# SensorsPower.net
KiCad netlist of a schematic drawn in Altium Designer
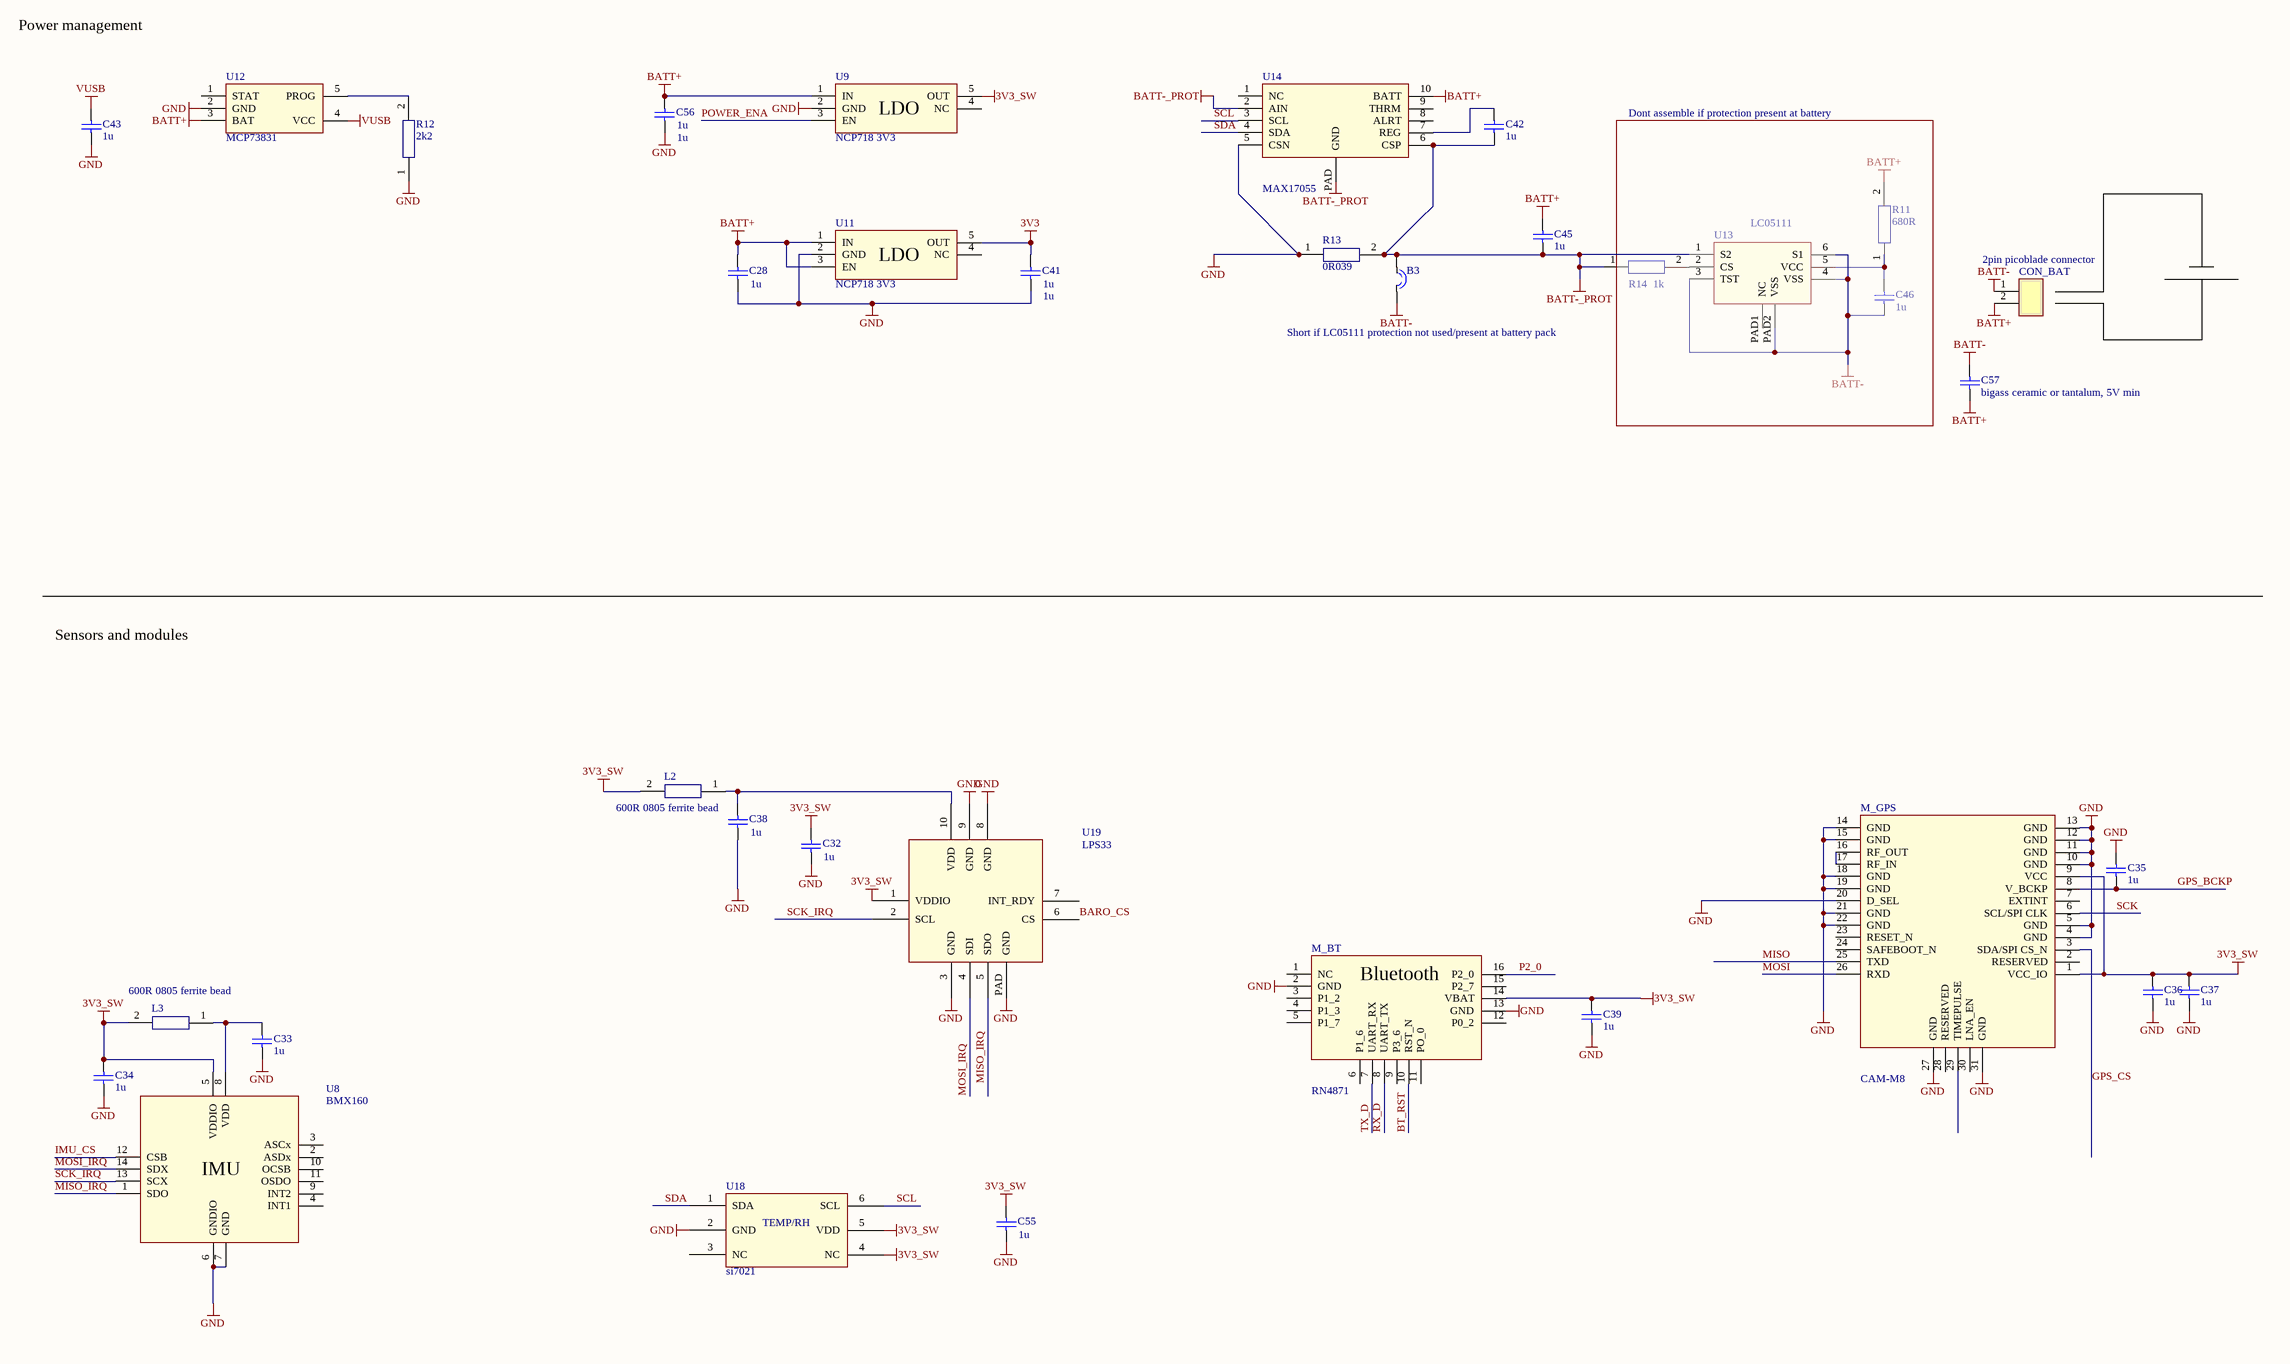
[diagram p0: SensorsPower.SchDoc]

(export (version "E")
  (design (tool "Eeschema 10.0.6"))
  (components
    (comp (ref "B3")
      (value "Short if LC05111 protection not used/present at battery pack")
      (footprint "Solder_bridge_small")
      (description "Solder bridge")
      (libsource (lib "xilinx") (part "Solder_bridge"))
    )
    (comp (ref "C28")
      (value "1u")
      (footprint "cap0603")
      (description "0603")
      (fields (field (name "PUBLISHER") "Altium Limited"))
      (libsource (lib "Miscellaneous Devices") (part "Cap"))
    )
    (comp (ref "C32")
      (value "1u")
      (footprint "cap0603")
      (description "0603")
      (fields (field (name "PUBLISHER") "Altium Limited"))
      (libsource (lib "Miscellaneous Devices") (part "Cap"))
    )
    (comp (ref "C33")
      (value "1u")
      (footprint "cap0603")
      (description "0603")
      (fields (field (name "PUBLISHER") "Altium Limited"))
      (libsource (lib "Miscellaneous Devices") (part "Cap"))
    )
    (comp (ref "C34")
      (value "1u")
      (footprint "cap0603")
      (description "0603")
      (fields (field (name "PUBLISHER") "Altium Limited"))
      (libsource (lib "Miscellaneous Devices") (part "Cap"))
    )
    (comp (ref "C35")
      (value "1u")
      (footprint "cap0603")
      (description "0603")
      (fields (field (name "PUBLISHER") "Altium Limited"))
      (libsource (lib "Miscellaneous Devices") (part "Cap"))
    )
    (comp (ref "C36")
      (value "1u")
      (footprint "cap0603")
      (description "0603")
      (fields (field (name "PUBLISHER") "Altium Limited"))
      (libsource (lib "Miscellaneous Devices") (part "Cap"))
    )
    (comp (ref "C37")
      (value "1u")
      (footprint "cap0603")
      (description "0603")
      (fields (field (name "PUBLISHER") "Altium Limited"))
      (libsource (lib "Miscellaneous Devices") (part "Cap"))
    )
    (comp (ref "C38")
      (value "1u")
      (footprint "cap0603")
      (description "0603")
      (fields (field (name "PUBLISHER") "Altium Limited"))
      (libsource (lib "Miscellaneous Devices") (part "Cap"))
    )
    (comp (ref "C39")
      (value "1u")
      (footprint "cap0603")
      (description "0603")
      (fields (field (name "PUBLISHER") "Altium Limited"))
      (libsource (lib "Miscellaneous Devices") (part "Cap"))
    )
    (comp (ref "C41")
      (value "1u")
      (footprint "cap0603")
      (description "0603")
      (fields (field (name "ALTIUM_VALUE") "1u") (field (name "PUBLISHER") "Altium Limited"))
      (libsource (lib "Miscellaneous Devices") (part "Cap"))
    )
    (comp (ref "C42")
      (value "1u")
      (footprint "cap0603")
      (description "0603")
      (fields (field (name "PUBLISHER") "Altium Limited"))
      (libsource (lib "Miscellaneous Devices") (part "Cap"))
    )
    (comp (ref "C43")
      (value "1u")
      (footprint "cap0603")
      (description "0603")
      (fields (field (name "PUBLISHER") "Altium Limited"))
      (libsource (lib "Miscellaneous Devices") (part "Cap"))
    )
    (comp (ref "C45")
      (value "1u")
      (footprint "cap0603")
      (description "0603")
      (fields (field (name "PUBLISHER") "Altium Limited"))
      (libsource (lib "Miscellaneous Devices") (part "Cap"))
    )
    (comp (ref "C46")
      (value "1u")
      (footprint "cap0603")
      (description "0603")
      (fields (field (name "PUBLISHER") "Altium Limited"))
      (libsource (lib "Miscellaneous Devices") (part "Cap"))
    )
    (comp (ref "C55")
      (value "1u")
      (footprint "cap0603")
      (description "0603")
      (fields (field (name "PUBLISHER") "Altium Limited"))
      (libsource (lib "Miscellaneous Devices") (part "Cap"))
    )
    (comp (ref "C56")
      (value "1u")
      (footprint "cap0603")
      (description "0603")
      (fields (field (name "ALTIUM_VALUE") "1u") (field (name "PUBLISHER") "Altium Limited"))
      (libsource (lib "Miscellaneous Devices") (part "Cap"))
    )
    (comp (ref "C57")
      (value "bigass ceramic or tantalum, 5V min")
      (footprint "CAP1206")
      (description "1206")
      (fields (field (name "PUBLISHER") "Altium Limited"))
      (libsource (lib "Miscellaneous Devices") (part "Cap"))
    )
    (comp (ref "CON_BAT")
      (value "2pin picoblade connector")
      (footprint "1x2, 1.25")
      (libsource (lib "headers") (part "1x2 Header, 2.54"))
    )
    (comp (ref "L2")
      (value "600R 0805 ferrite bead")
      (footprint "cap0805")
      (description "0805")
      (libsource (lib "PassiveSMT") (part "Resistor1"))
    )
    (comp (ref "L3")
      (value "600R 0805 ferrite bead")
      (footprint "cap0805")
      (description "0805")
      (libsource (lib "PassiveSMT") (part "Resistor1"))
    )
    (comp (ref "M_BT")
      (value "RN4871")
      (footprint "RN4871")
      (description "bluetooth module")
      (libsource (lib "xilinx") (part "RN4871"))
    )
    (comp (ref "M_GPS")
      (value "CAM-M8")
      (footprint "CAM")
      (description "u-blox CAM GNSS antenna module")
      (fields (field (name "MANUFACTURER") "u-blox"))
      (libsource (lib "ubloxLib") (part "CAM-M8"))
    )
    (comp (ref "R11")
      (value "680R")
      (footprint "cap0805")
      (description "0805")
      (libsource (lib "PassiveSMT") (part "Resistor1"))
    )
    (comp (ref "R12")
      (value "2k2")
      (footprint "cap0805")
      (description "0805")
      (libsource (lib "PassiveSMT") (part "Resistor1"))
    )
    (comp (ref "R13")
      (value "0R039")
      (footprint "cap0805")
      (description "0805")
      (libsource (lib "PassiveSMT") (part "Resistor1"))
    )
    (comp (ref "R14")
      (value "1k")
      (footprint "cap0805")
      (description "0805")
      (libsource (lib "PassiveSMT") (part "Resistor1"))
    )
    (comp (ref "U8")
      (value "BMX160")
      (footprint "LGA14 3*2.5")
      (description "IMU mems unit")
      (libsource (lib "xilinx") (part "BMX160"))
    )
    (comp (ref "U9")
      (value "NCP718 3V3")
      (footprint "sot23-5")
      (description "SOT23 3.3V LDO regulator")
      (libsource (lib "xilinx") (part "LDLN025 LDO"))
    )
    (comp (ref "U11")
      (value "NCP718 3V3")
      (footprint "sot23-5")
      (description "SOT23 3.3V LDO regulator")
      (libsource (lib "xilinx") (part "LDLN025 LDO"))
    )
    (comp (ref "U12")
      (value "MCP73831")
      (footprint "sot23-5")
      (description "SOT23 linear battery charging controller")
      (libsource (lib "xilinx") (part "MCP73831"))
    )
    (comp (ref "U13")
      (value "LC05111")
      (footprint "wdfn6_dual_flag")
      (description "Battery protection circuit")
      (libsource (lib "xilinx") (part "LC05111"))
    )
    (comp (ref "U14")
      (value "MAX17055")
      (footprint "tdfn10_ep")
      (description "Battery monitoring gauge")
      (libsource (lib "xilinx") (part "MAX17055"))
    )
    (comp (ref "U18")
      (value "si7021")
      (footprint "dfn6")
      (description "temp and humidity sensor")
      (libsource (lib "xilinx") (part "SHT21"))
    )
    (comp (ref "U19")
      (value "LPS33")
      (footprint "LPS33")
      (description "barometer")
      (libsource (lib "xilinx") (part "LPS33"))
    )
  )
  (nets
    (net (code "1") (name "/BARO_CS") (class "Default")
      (node (ref "U19") (pin "6") (pinfunction "CS_6") (pintype "passive"))
    )
    (net (code "2") (name "/BT_RST") (class "Default")
      (node (ref "M_BT") (pin "10") (pinfunction "RST_N_10") (pintype "passive"))
    )
    (net (code "3") (name "/GPS_BCKP") (class "Default")
      (node (ref "C35") (pin "2") (pinfunction "2_2") (pintype "passive"))
      (node (ref "M_GPS") (pin "8") (pinfunction "V_BCKP_8") (pintype "passive"))
    )
    (net (code "4") (name "/GPS_CS") (class "Default")
      (node (ref "M_GPS") (pin "3") (pinfunction "SDA/SPI_CS_N_3") (pintype "passive"))
    )
    (net (code "5") (name "/IMU_CS") (class "Default")
      (node (ref "U8") (pin "12") (pinfunction "CSB_12") (pintype "passive"))
    )
    (net (code "6") (name "/MISO") (class "Default")
      (node (ref "M_GPS") (pin "25") (pinfunction "TXD_25") (pintype "passive"))
    )
    (net (code "7") (name "/MISO_IRQ") (class "Default")
      (node (ref "U19") (pin "5") (pinfunction "SDO_5") (pintype "passive"))
      (node (ref "U8") (pin "1") (pinfunction "SDO_1") (pintype "passive"))
    )
    (net (code "8") (name "/MOSI") (class "Default")
      (node (ref "M_GPS") (pin "26") (pinfunction "RXD_26") (pintype "passive"))
    )
    (net (code "9") (name "/MOSI_IRQ") (class "Default")
      (node (ref "U19") (pin "4") (pinfunction "SDI_4") (pintype "passive"))
      (node (ref "U8") (pin "14") (pinfunction "SDX_14") (pintype "passive"))
    )
    (net (code "10") (name "/P2_0") (class "Default")
      (node (ref "M_BT") (pin "16") (pinfunction "P2_0_16") (pintype "passive"))
    )
    (net (code "11") (name "/POWER_ENA") (class "Default")
      (node (ref "U9") (pin "3") (pinfunction "EN_3") (pintype "passive"))
    )
    (net (code "12") (name "/RX_D") (class "Default")
      (node (ref "M_BT") (pin "8") (pinfunction "UART_TX_8") (pintype "passive"))
    )
    (net (code "13") (name "/SCK") (class "Default")
      (node (ref "M_GPS") (pin "6") (pinfunction "SCL/SPI_CLK_6") (pintype "passive"))
    )
    (net (code "14") (name "/SCK_IRQ") (class "Default")
      (node (ref "U19") (pin "2") (pinfunction "SCL_2") (pintype "passive"))
      (node (ref "U8") (pin "13") (pinfunction "SCX_13") (pintype "passive"))
    )
    (net (code "15") (name "/SCL") (class "Default")
      (node (ref "U14") (pin "3") (pinfunction "SCL_3") (pintype "passive"))
      (node (ref "U18") (pin "6") (pinfunction "SCL_6") (pintype "passive"))
    )
    (net (code "16") (name "/SDA") (class "Default")
      (node (ref "U14") (pin "4") (pinfunction "SDA_4") (pintype "passive"))
      (node (ref "U18") (pin "1") (pinfunction "SDA_1") (pintype "passive"))
    )
    (net (code "17") (name "/TX_D") (class "Default")
      (node (ref "M_BT") (pin "7") (pinfunction "UART_RX_7") (pintype "passive"))
    )
    (net (code "18") (name "3V3") (class "Default")
      (node (ref "C41") (pin "2") (pinfunction "2_2") (pintype "passive"))
      (node (ref "U11") (pin "5") (pinfunction "OUT_5") (pintype "passive"))
    )
    (net (code "19") (name "3V3_SW") (class "Default")
      (node (ref "C32") (pin "2") (pinfunction "2_2") (pintype "passive"))
      (node (ref "C34") (pin "2") (pinfunction "2_2") (pintype "passive"))
      (node (ref "C36") (pin "1") (pinfunction "1_1") (pintype "passive"))
      (node (ref "C37") (pin "1") (pinfunction "1_1") (pintype "passive"))
      (node (ref "C39") (pin "1") (pinfunction "1_1") (pintype "passive"))
      (node (ref "C55") (pin "2") (pinfunction "2_2") (pintype "passive"))
      (node (ref "L2") (pin "2") (pinfunction "2_2") (pintype "passive"))
      (node (ref "L3") (pin "2") (pinfunction "2_2") (pintype "passive"))
      (node (ref "M_BT") (pin "14") (pinfunction "VBAT_14") (pintype "passive"))
      (node (ref "M_GPS") (pin "1") (pinfunction "VCC_IO_1") (pintype "passive"))
      (node (ref "M_GPS") (pin "9") (pinfunction "VCC_9") (pintype "passive"))
      (node (ref "U18") (pin "4") (pinfunction "NC_4") (pintype "passive"))
      (node (ref "U18") (pin "5") (pinfunction "VDD_5") (pintype "passive"))
      (node (ref "U19") (pin "1") (pinfunction "VDDIO_1") (pintype "passive"))
      (node (ref "U8") (pin "5") (pinfunction "VDDIO_5") (pintype "passive"))
      (node (ref "U9") (pin "5") (pinfunction "OUT_5") (pintype "passive"))
    )
    (net (code "20") (name "BATT+") (class "Default")
      (node (ref "C28") (pin "2") (pinfunction "2_2") (pintype "passive"))
      (node (ref "C45") (pin "2") (pinfunction "2_2") (pintype "passive"))
      (node (ref "C56") (pin "2") (pinfunction "2_2") (pintype "passive"))
      (node (ref "C57") (pin "1") (pinfunction "1_1") (pintype "passive"))
      (node (ref "CON_BAT") (pin "2") (pinfunction "2_2") (pintype "passive"))
      (node (ref "R11") (pin "2") (pinfunction "2_2") (pintype "passive"))
      (node (ref "U11") (pin "1") (pinfunction "IN_1") (pintype "passive"))
      (node (ref "U11") (pin "3") (pinfunction "EN_3") (pintype "passive"))
      (node (ref "U12") (pin "3") (pinfunction "BAT_3") (pintype "passive"))
      (node (ref "U14") (pin "10") (pinfunction "BATT_10") (pintype "passive"))
      (node (ref "U9") (pin "1") (pinfunction "IN_1") (pintype "passive"))
    )
    (net (code "21") (name "BATT-") (class "Default")
      (node (ref "B3") (pin "1") (pinfunction "1_1") (pintype "passive"))
      (node (ref "C46") (pin "1") (pinfunction "1_1") (pintype "passive"))
      (node (ref "C57") (pin "2") (pinfunction "2_2") (pintype "passive"))
      (node (ref "CON_BAT") (pin "1") (pinfunction "1_1") (pintype "passive"))
      (node (ref "U13") (pin "3") (pinfunction "TST_3") (pintype "passive"))
      (node (ref "U13") (pin "4") (pinfunction "VSS_4") (pintype "passive"))
      (node (ref "U13") (pin "6") (pinfunction "S1_6") (pintype "passive"))
      (node (ref "U13") (pin "PAD2") (pinfunction "VSS_PAD2") (pintype "passive"))
    )
    (net (code "22") (name "BATT-_PROT") (class "Default")
      (node (ref "B3") (pin "2") (pinfunction "2_2") (pintype "passive"))
      (node (ref "C42") (pin "1") (pinfunction "1_1") (pintype "passive"))
      (node (ref "C45") (pin "1") (pinfunction "1_1") (pintype "passive"))
      (node (ref "R13") (pin "2") (pinfunction "2_2") (pintype "passive"))
      (node (ref "R14") (pin "1") (pinfunction "1_1") (pintype "passive"))
      (node (ref "U13") (pin "1") (pinfunction "S2_1") (pintype "passive"))
      (node (ref "U14") (pin "2") (pinfunction "AIN_2") (pintype "passive"))
      (node (ref "U14") (pin "6") (pinfunction "CSP_6") (pintype "passive"))
      (node (ref "U14") (pin "PAD") (pinfunction "GND_PAD") (pintype "passive"))
    )
    (net (code "23") (name "GND") (class "Default")
      (node (ref "C28") (pin "1") (pinfunction "1_1") (pintype "passive"))
      (node (ref "C32") (pin "1") (pinfunction "1_1") (pintype "passive"))
      (node (ref "C33") (pin "1") (pinfunction "1_1") (pintype "passive"))
      (node (ref "C34") (pin "1") (pinfunction "1_1") (pintype "passive"))
      (node (ref "C35") (pin "1") (pinfunction "1_1") (pintype "passive"))
      (node (ref "C36") (pin "2") (pinfunction "2_2") (pintype "passive"))
      (node (ref "C37") (pin "2") (pinfunction "2_2") (pintype "passive"))
      (node (ref "C38") (pin "1") (pinfunction "1_1") (pintype "passive"))
      (node (ref "C39") (pin "2") (pinfunction "2_2") (pintype "passive"))
      (node (ref "C41") (pin "1") (pinfunction "1_1") (pintype "passive"))
      (node (ref "C43") (pin "1") (pinfunction "1_1") (pintype "passive"))
      (node (ref "C55") (pin "1") (pinfunction "1_1") (pintype "passive"))
      (node (ref "C56") (pin "1") (pinfunction "1_1") (pintype "passive"))
      (node (ref "M_BT") (pin "13") (pinfunction "GND_13") (pintype "passive"))
      (node (ref "M_BT") (pin "2") (pinfunction "GND_2") (pintype "passive"))
      (node (ref "M_GPS") (pin "10") (pinfunction "GND_10") (pintype "passive"))
      (node (ref "M_GPS") (pin "11") (pinfunction "GND_11") (pintype "passive"))
      (node (ref "M_GPS") (pin "12") (pinfunction "GND_12") (pintype "passive"))
      (node (ref "M_GPS") (pin "13") (pinfunction "GND_13") (pintype "passive"))
      (node (ref "M_GPS") (pin "14") (pinfunction "GND_14") (pintype "passive"))
      (node (ref "M_GPS") (pin "15") (pinfunction "GND_15") (pintype "passive"))
      (node (ref "M_GPS") (pin "18") (pinfunction "GND_18") (pintype "passive"))
      (node (ref "M_GPS") (pin "19") (pinfunction "GND_19") (pintype "passive"))
      (node (ref "M_GPS") (pin "20") (pinfunction "D_SEL_20") (pintype "passive"))
      (node (ref "M_GPS") (pin "21") (pinfunction "GND_21") (pintype "passive"))
      (node (ref "M_GPS") (pin "22") (pinfunction "GND_22") (pintype "passive"))
      (node (ref "M_GPS") (pin "27") (pinfunction "GND_27") (pintype "passive"))
      (node (ref "M_GPS") (pin "31") (pinfunction "GND_31") (pintype "passive"))
      (node (ref "M_GPS") (pin "4") (pinfunction "GND_4") (pintype "passive"))
      (node (ref "M_GPS") (pin "5") (pinfunction "GND_5") (pintype "passive"))
      (node (ref "R12") (pin "1") (pinfunction "1_1") (pintype "passive"))
      (node (ref "R13") (pin "1") (pinfunction "1_1") (pintype "passive"))
      (node (ref "U11") (pin "2") (pinfunction "GND_2") (pintype "passive"))
      (node (ref "U12") (pin "2") (pinfunction "GND_2") (pintype "passive"))
      (node (ref "U14") (pin "5") (pinfunction "CSN_5") (pintype "passive"))
      (node (ref "U18") (pin "2") (pinfunction "GND_2") (pintype "passive"))
      (node (ref "U19") (pin "3") (pinfunction "GND_3") (pintype "passive"))
      (node (ref "U19") (pin "8") (pinfunction "GND_8") (pintype "passive"))
      (node (ref "U19") (pin "9") (pinfunction "GND_9") (pintype "passive"))
      (node (ref "U19") (pin "PAD") (pinfunction "GND_PAD") (pintype "passive"))
      (node (ref "U8") (pin "6") (pinfunction "GNDIO_6") (pintype "passive"))
      (node (ref "U8") (pin "7") (pinfunction "GND_7") (pintype "passive"))
      (node (ref "U9") (pin "2") (pinfunction "GND_2") (pintype "passive"))
    )
    (net (code "24") (name "Net-(M_GPS-RF_IN)") (class "Default")
      (node (ref "M_GPS") (pin "16") (pinfunction "RF_OUT_16") (pintype "passive"))
      (node (ref "M_GPS") (pin "17") (pinfunction "RF_IN_17") (pintype "passive"))
    )
    (net (code "25") (name "Net-(U8-VDD)") (class "Default")
      (node (ref "C33") (pin "2") (pinfunction "2_2") (pintype "passive"))
      (node (ref "L3") (pin "1") (pinfunction "1_1") (pintype "passive"))
      (node (ref "U8") (pin "8") (pinfunction "VDD_8") (pintype "passive"))
    )
    (net (code "26") (name "Net-(U12-PROG)") (class "Default")
      (node (ref "R12") (pin "2") (pinfunction "2_2") (pintype "passive"))
      (node (ref "U12") (pin "5") (pinfunction "PROG_5") (pintype "passive"))
    )
    (net (code "27") (name "Net-(U13-CS)") (class "Default")
      (node (ref "R14") (pin "2") (pinfunction "2_2") (pintype "passive"))
      (node (ref "U13") (pin "2") (pinfunction "CS_2") (pintype "passive"))
    )
    (net (code "28") (name "Net-(U13-VCC)") (class "Default")
      (node (ref "C46") (pin "2") (pinfunction "2_2") (pintype "passive"))
      (node (ref "R11") (pin "1") (pinfunction "1_1") (pintype "passive"))
      (node (ref "U13") (pin "5") (pinfunction "VCC_5") (pintype "passive"))
    )
    (net (code "29") (name "Net-(U14-REG)") (class "Default")
      (node (ref "C42") (pin "2") (pinfunction "2_2") (pintype "passive"))
      (node (ref "U14") (pin "7") (pinfunction "REG_7") (pintype "passive"))
    )
    (net (code "30") (name "Net-(U19-VDD)") (class "Default")
      (node (ref "C38") (pin "2") (pinfunction "2_2") (pintype "passive"))
      (node (ref "L2") (pin "1") (pinfunction "1_1") (pintype "passive"))
      (node (ref "U19") (pin "10") (pinfunction "VDD_10") (pintype "passive"))
    )
    (net (code "31") (name "VUSB") (class "Default")
      (node (ref "C43") (pin "2") (pinfunction "2_2") (pintype "passive"))
      (node (ref "U12") (pin "4") (pinfunction "VCC_4") (pintype "passive"))
    )
    (net (code "32") (name "unconnected-(M_BT-NC-Pad1)") (class "Default")
      (node (ref "M_BT") (pin "1") (pinfunction "NC_1") (pintype "passive"))
    )
    (net (code "33") (name "unconnected-(M_BT-P0_2-Pad12)") (class "Default")
      (node (ref "M_BT") (pin "12") (pinfunction "P0_2_12") (pintype "passive"))
    )
    (net (code "34") (name "unconnected-(M_BT-P1_2-Pad3)") (class "Default")
      (node (ref "M_BT") (pin "3") (pinfunction "P1_2_3") (pintype "passive"))
    )
    (net (code "35") (name "unconnected-(M_BT-P1_3-Pad4)") (class "Default")
      (node (ref "M_BT") (pin "4") (pinfunction "P1_3_4") (pintype "passive"))
    )
    (net (code "36") (name "unconnected-(M_BT-P1_6-Pad6)") (class "Default")
      (node (ref "M_BT") (pin "6") (pinfunction "P1_6_6") (pintype "passive"))
    )
    (net (code "37") (name "unconnected-(M_BT-P1_7-Pad5)") (class "Default")
      (node (ref "M_BT") (pin "5") (pinfunction "P1_7_5") (pintype "passive"))
    )
    (net (code "38") (name "unconnected-(M_BT-P2_7-Pad15)") (class "Default")
      (node (ref "M_BT") (pin "15") (pinfunction "P2_7_15") (pintype "passive"))
    )
    (net (code "39") (name "unconnected-(M_BT-P3_6-Pad9)") (class "Default")
      (node (ref "M_BT") (pin "9") (pinfunction "P3_6_9") (pintype "passive"))
    )
    (net (code "40") (name "unconnected-(M_BT-PO_0-Pad11)") (class "Default")
      (node (ref "M_BT") (pin "11") (pinfunction "PO_0_11") (pintype "passive"))
    )
    (net (code "41") (name "unconnected-(M_GPS-EXTINT-Pad7)") (class "Default")
      (node (ref "M_GPS") (pin "7") (pinfunction "EXTINT_7") (pintype "passive"))
    )
    (net (code "42") (name "unconnected-(M_GPS-LNA_EN-Pad30)") (class "Default")
      (node (ref "M_GPS") (pin "30") (pinfunction "LNA_EN_30") (pintype "passive"))
    )
    (net (code "43") (name "unconnected-(M_GPS-RESERVED-Pad2)") (class "Default")
      (node (ref "M_GPS") (pin "2") (pinfunction "RESERVED_2") (pintype "passive"))
    )
    (net (code "44") (name "unconnected-(M_GPS-RESERVED-Pad28)") (class "Default")
      (node (ref "M_GPS") (pin "28") (pinfunction "RESERVED_28") (pintype "passive"))
    )
    (net (code "45") (name "unconnected-(M_GPS-RESET_N-Pad23)") (class "Default")
      (node (ref "M_GPS") (pin "23") (pinfunction "RESET_N_23") (pintype "passive"))
    )
    (net (code "46") (name "unconnected-(M_GPS-SAFEBOOT_N-Pad24)") (class "Default")
      (node (ref "M_GPS") (pin "24") (pinfunction "SAFEBOOT_N_24") (pintype "passive"))
    )
    (net (code "47") (name "unconnected-(M_GPS-TIMEPULSE-Pad29)") (class "Default")
      (node (ref "M_GPS") (pin "29") (pinfunction "TIMEPULSE_29") (pintype "passive"))
    )
    (net (code "48") (name "unconnected-(U8-ASCx-Pad3)") (class "Default")
      (node (ref "U8") (pin "3") (pinfunction "ASCx_3") (pintype "passive"))
    )
    (net (code "49") (name "unconnected-(U8-ASDx-Pad2)") (class "Default")
      (node (ref "U8") (pin "2") (pinfunction "ASDx_2") (pintype "passive"))
    )
    (net (code "50") (name "unconnected-(U8-INT1-Pad4)") (class "Default")
      (node (ref "U8") (pin "4") (pinfunction "INT1_4") (pintype "passive"))
    )
    (net (code "51") (name "unconnected-(U8-INT2-Pad9)") (class "Default")
      (node (ref "U8") (pin "9") (pinfunction "INT2_9") (pintype "passive"))
    )
    (net (code "52") (name "unconnected-(U8-OCSB-Pad10)") (class "Default")
      (node (ref "U8") (pin "10") (pinfunction "OCSB_10") (pintype "passive"))
    )
    (net (code "53") (name "unconnected-(U8-OSDO-Pad11)") (class "Default")
      (node (ref "U8") (pin "11") (pinfunction "OSDO_11") (pintype "passive"))
    )
    (net (code "54") (name "unconnected-(U9-NC-Pad4)") (class "Default")
      (node (ref "U9") (pin "4") (pinfunction "NC_4") (pintype "passive"))
    )
    (net (code "55") (name "unconnected-(U11-NC-Pad4)") (class "Default")
      (node (ref "U11") (pin "4") (pinfunction "NC_4") (pintype "passive"))
    )
    (net (code "56") (name "unconnected-(U12-STAT-Pad1)") (class "Default")
      (node (ref "U12") (pin "1") (pinfunction "STAT_1") (pintype "passive"))
    )
    (net (code "57") (name "unconnected-(U13-NC-PadPAD1)") (class "Default")
      (node (ref "U13") (pin "PAD1") (pinfunction "NC_PAD1") (pintype "passive"))
    )
    (net (code "58") (name "unconnected-(U14-ALRT-Pad8)") (class "Default")
      (node (ref "U14") (pin "8") (pinfunction "ALRT_8") (pintype "passive"))
    )
    (net (code "59") (name "unconnected-(U14-NC-Pad1)") (class "Default")
      (node (ref "U14") (pin "1") (pinfunction "NC_1") (pintype "passive"))
    )
    (net (code "60") (name "unconnected-(U14-THRM-Pad9)") (class "Default")
      (node (ref "U14") (pin "9") (pinfunction "THRM_9") (pintype "passive"))
    )
    (net (code "61") (name "unconnected-(U18-NC-Pad3)") (class "Default")
      (node (ref "U18") (pin "3") (pinfunction "NC_3") (pintype "passive"))
    )
    (net (code "62") (name "unconnected-(U19-INT_RDY-Pad7)") (class "Default")
      (node (ref "U19") (pin "7") (pinfunction "INT_RDY_7") (pintype "passive"))
    )
  )
)
